# ACCEL.net
KiCad netlist of a schematic drawn in Altium Designer
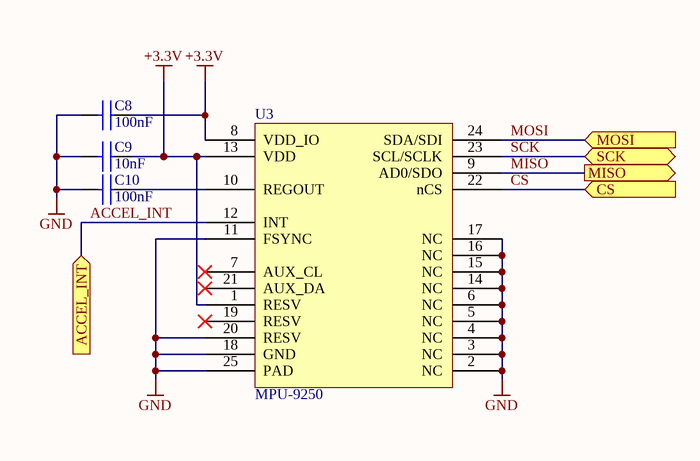
[diagram p0: ACCEL.SchDoc]

(export (version "E")
  (design (tool "Eeschema 10.0.6"))
  (components
    (comp (ref "C8")
      (value "100nF")
      (footprint "CAP0603")
      (description "MURATA - GRM188R71C104KA01J - CAP, MLCC, X7R, 0.1UF, 16V, 0603")
      (fields
        (field (name "MANUFACTURER") "MURATA")
        (field (name "MANUFACTURER PART NUMBER") "GRM188R71C104KA01J")
      )
      (libsource (lib "Passive") (part "C - 100nF"))
    )
    (comp (ref "C9")
      (value "10nF")
      (footprint "CAP0603")
      (description "KEMET - C0603X103K5RECAUTO - CAP, MLCC, AEC-Q200, X7R, 0.01UF, 50V")
      (fields
        (field (name "MANUFACTURER") "TDK EPCOS")
        (field (name "MANUFACTURER PART NUMBER") "C0603X103K5RECAUTO")
      )
      (libsource (lib "Passive") (part "C - 10nF"))
    )
    (comp (ref "C10")
      (value "100nF")
      (footprint "CAP0603")
      (description "MURATA - GRM188R71C104KA01J - CAP, MLCC, X7R, 0.1UF, 16V, 0603")
      (fields
        (field (name "MANUFACTURER") "MURATA")
        (field (name "MANUFACTURER PART NUMBER") "GRM188R71C104KA01J")
      )
      (libsource (lib "Passive") (part "C - 100nF"))
    )
    (comp (ref "U3")
      (value "MPU-9250")
      (footprint "QFN40P300X300X105_HS-25N")
      (description "IMU ACCEL/GYRO/MAG I2C/SPI 24QFN")
      (fields (field (name "MANUFACTURER") "TDK InvenSense"))
      (libsource (lib "Active") (part "SEN - MPU-9250"))
    )
  )
  (nets
    (net (code "1") (name "+3.3V") (class "Default")
      (node (ref "C8") (pin "1") (pinfunction "1_1") (pintype "passive"))
      (node (ref "C9") (pin "1") (pinfunction "1_1") (pintype "passive"))
      (node (ref "U3") (pin "1") (pinfunction "RESV_1") (pintype "passive"))
      (node (ref "U3") (pin "13") (pinfunction "VDD_13") (pintype "passive"))
      (node (ref "U3") (pin "8") (pinfunction "VDD_IO_8") (pintype "passive"))
    )
    (net (code "2") (name "/ACCEL_INT") (class "Default")
      (node (ref "U3") (pin "12") (pinfunction "INT_12") (pintype "passive"))
    )
    (net (code "3") (name "/CS") (class "Default")
      (node (ref "U3") (pin "22") (pinfunction "nCS_22") (pintype "passive"))
    )
    (net (code "4") (name "/MISO") (class "Default")
      (node (ref "U3") (pin "9") (pinfunction "AD0/SDO_9") (pintype "passive"))
    )
    (net (code "5") (name "/MOSI") (class "Default")
      (node (ref "U3") (pin "24") (pinfunction "SDA/SDI_24") (pintype "passive"))
    )
    (net (code "6") (name "/SCK") (class "Default")
      (node (ref "U3") (pin "23") (pinfunction "SCL/SCLK_23") (pintype "passive"))
    )
    (net (code "7") (name "GND") (class "Default")
      (node (ref "C10") (pin "2") (pinfunction "2_2") (pintype "passive"))
      (node (ref "C8") (pin "2") (pinfunction "2_2") (pintype "passive"))
      (node (ref "C9") (pin "2") (pinfunction "2_2") (pintype "passive"))
      (node (ref "U3") (pin "11") (pinfunction "FSYNC_11") (pintype "passive"))
      (node (ref "U3") (pin "14") (pinfunction "NC_14") (pintype "passive"))
      (node (ref "U3") (pin "15") (pinfunction "NC_15") (pintype "passive"))
      (node (ref "U3") (pin "16") (pinfunction "NC_16") (pintype "passive"))
      (node (ref "U3") (pin "17") (pinfunction "NC_17") (pintype "passive"))
      (node (ref "U3") (pin "18") (pinfunction "GND_18") (pintype "passive"))
      (node (ref "U3") (pin "2") (pinfunction "NC_2") (pintype "passive"))
      (node (ref "U3") (pin "20") (pinfunction "RESV_20") (pintype "passive"))
      (node (ref "U3") (pin "25") (pinfunction "PAD_25") (pintype "passive"))
      (node (ref "U3") (pin "3") (pinfunction "NC_3") (pintype "passive"))
      (node (ref "U3") (pin "4") (pinfunction "NC_4") (pintype "passive"))
      (node (ref "U3") (pin "5") (pinfunction "NC_5") (pintype "passive"))
      (node (ref "U3") (pin "6") (pinfunction "NC_6") (pintype "passive"))
    )
    (net (code "8") (name "Net-(U3-REGOUT)") (class "Default")
      (node (ref "C10") (pin "1") (pinfunction "1_1") (pintype "passive"))
      (node (ref "U3") (pin "10") (pinfunction "REGOUT_10") (pintype "passive"))
    )
    (net (code "9") (name "unconnected-(U3-AUX_CL-Pad7)") (class "Default")
      (node (ref "U3") (pin "7") (pinfunction "AUX_CL_7") (pintype "passive+no_connect"))
    )
    (net (code "10") (name "unconnected-(U3-AUX_DA-Pad21)") (class "Default")
      (node (ref "U3") (pin "21") (pinfunction "AUX_DA_21") (pintype "passive+no_connect"))
    )
    (net (code "11") (name "unconnected-(U3-RESV-Pad19)") (class "Default")
      (node (ref "U3") (pin "19") (pinfunction "RESV_19") (pintype "passive+no_connect"))
    )
  )
)
